# pca20053_sheet2_nrf5340_mcu.net
KiCad netlist of a schematic drawn in Altium Designer
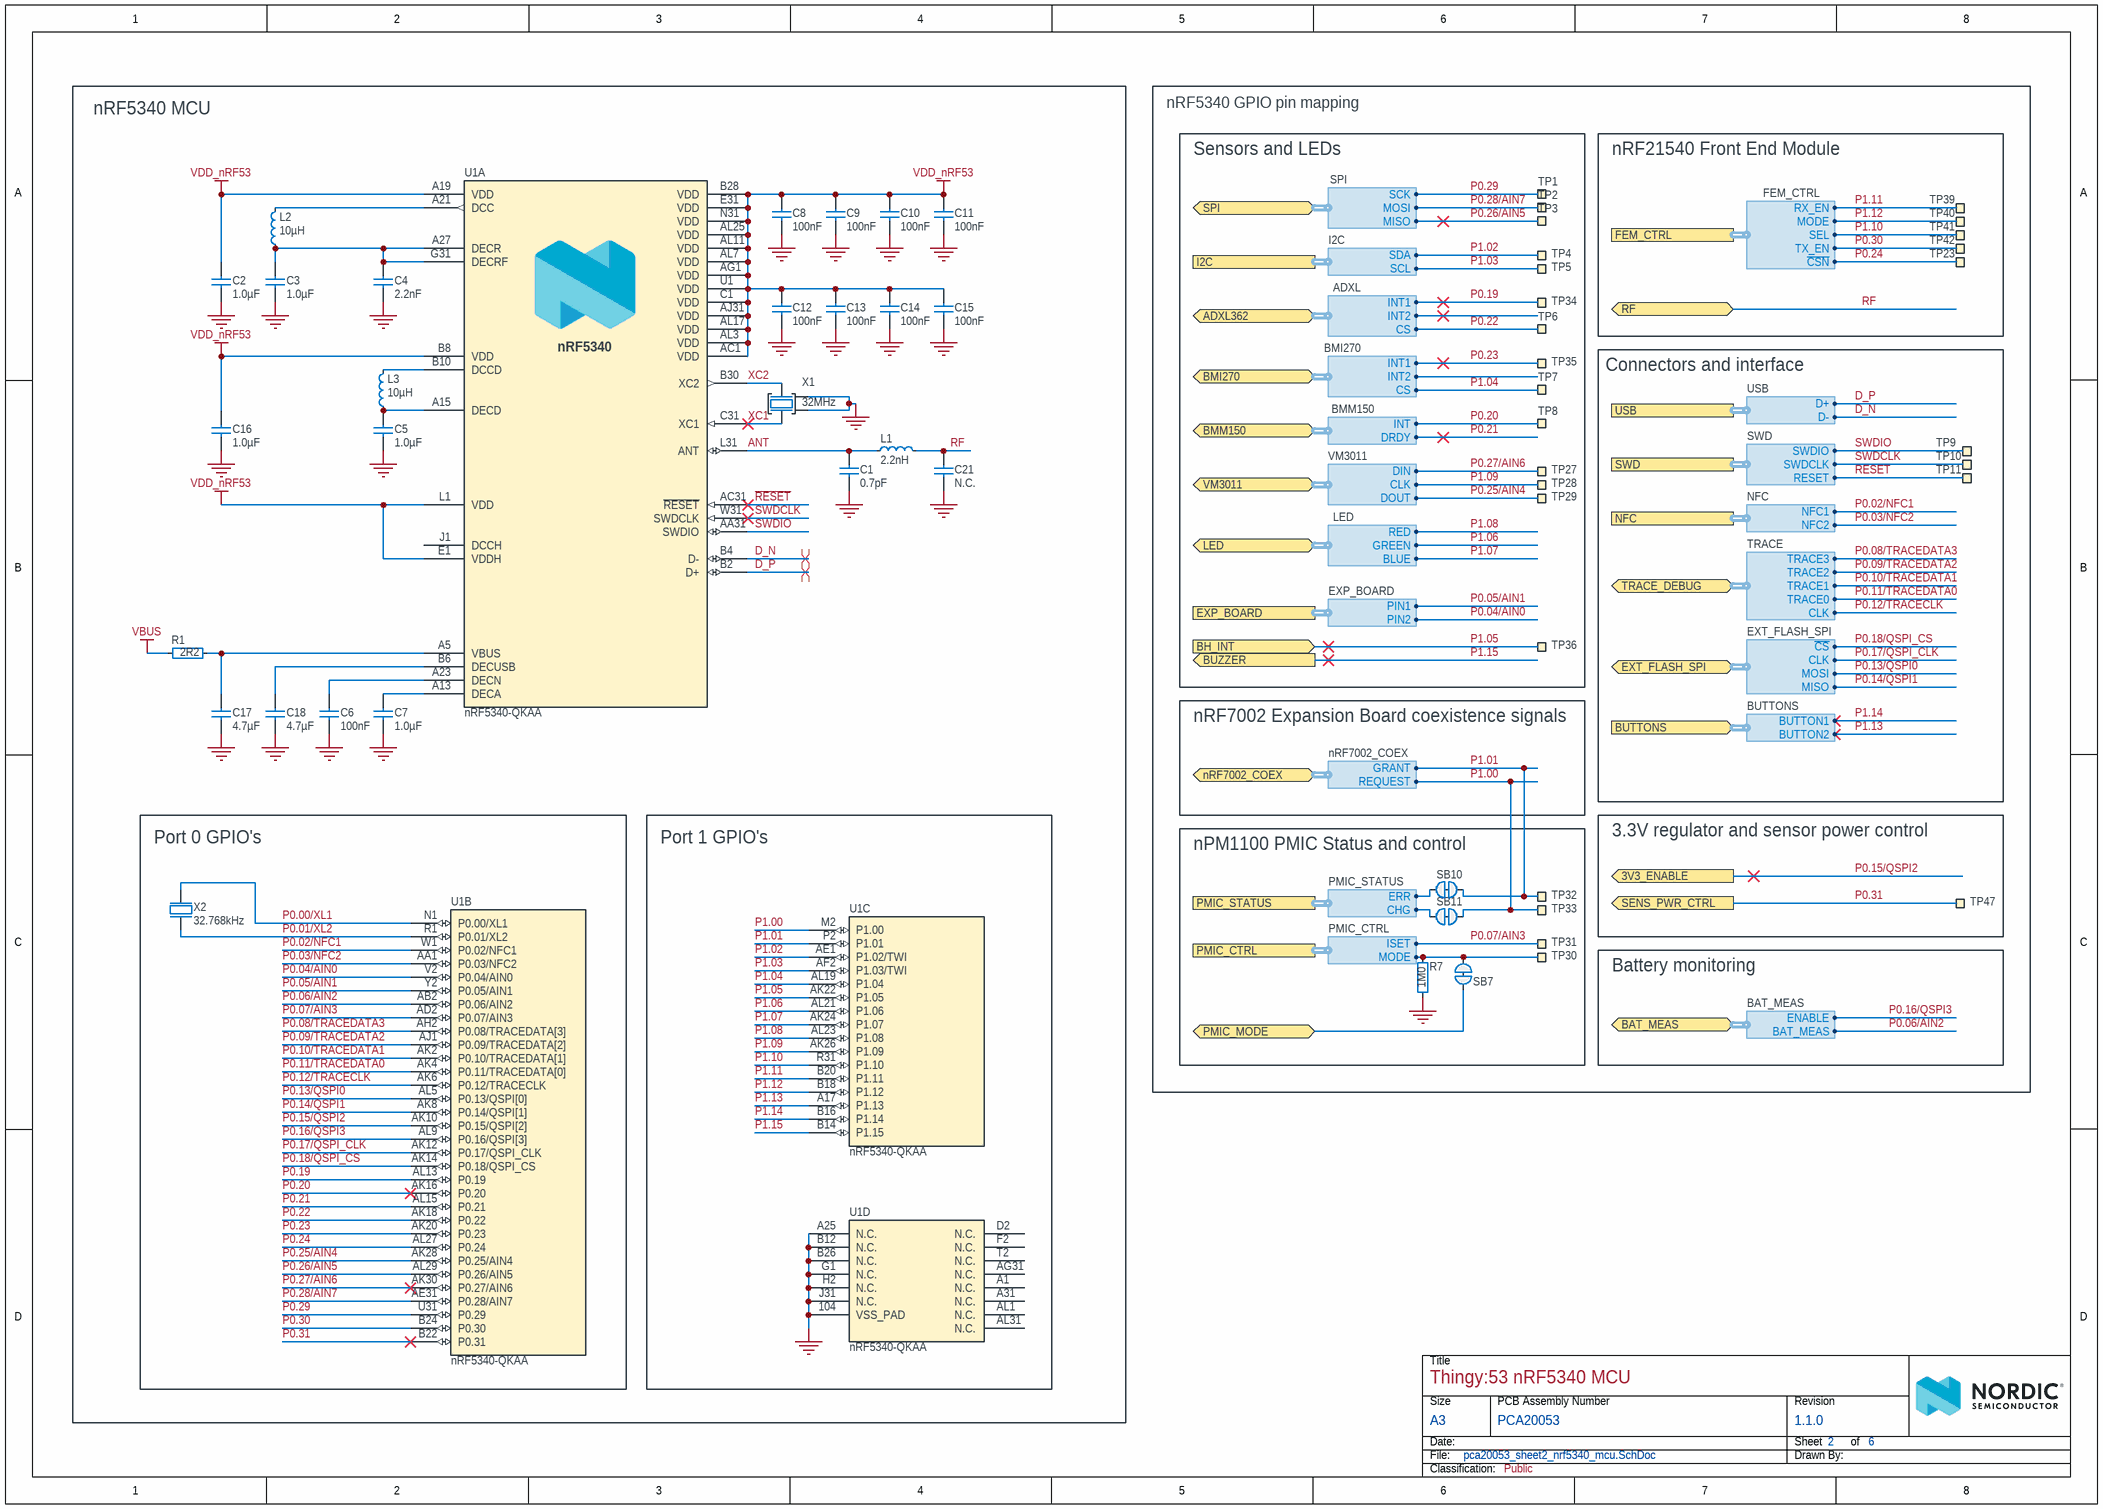
[diagram p0: pca20053_sheet2_nrf5340_mcu.SchDoc]

(export (version "E")
  (design (tool "Eeschema 10.0.6"))
  (components
    (comp (ref "C1")
      (value "0.7pF")
      (footprint "CAPC0603X03L_C")
      (description "Capacitor, Ceramic, C0G, ±0.05pF, 50V")
      (fields
        (field (name "PART NUMBER") "C0201-0.7p-50V-C0G-GJM0335C1HR70WB01")
        (field (name "MANUFACTURER") "Murata")
        (field (name "AUTHOR") "rsk")
      )
      (libsource (lib "AltiumLib") (part "CAP"))
    )
    (comp (ref "C2")
      (value "1.0µF")
      (footprint "CAPC1005X04L")
      (description "Capacitor, Ceramic, X5R, ±10%, 25V")
      (fields
        (field (name "PART NUMBER") "C0402-1µ0-25V-X5R")
        (field (name "MANUFACTURER") "Murata")
        (field (name "AUTHOR") "rsk")
      )
      (libsource (lib "AltiumLib") (part "CAP"))
    )
    (comp (ref "C3")
      (value "1.0µF")
      (footprint "CAPC1005X04L")
      (description "Capacitor, Ceramic, X5R, ±10%, 25V")
      (fields
        (field (name "PART NUMBER") "C0402-1µ0-25V-X5R")
        (field (name "MANUFACTURER") "Murata")
        (field (name "AUTHOR") "rsk")
      )
      (libsource (lib "AltiumLib") (part "CAP"))
    )
    (comp (ref "C4")
      (value "2.2nF")
      (footprint "CAPC0603X03L_C")
      (description "Capacitor, Ceramic, X5R, ±10%, 10V")
      (fields
        (field (name "PART NUMBER") "C0201-2n2-10V-X5R")
        (field (name "MANUFACTURER") "Murata")
        (field (name "AUTHOR") "rsk")
      )
      (libsource (lib "AltiumLib") (part "CAP"))
    )
    (comp (ref "C5")
      (value "1.0µF")
      (footprint "CAPC1005X04L")
      (description "Capacitor, Ceramic, X5R, ±10%, 25V")
      (fields
        (field (name "PART NUMBER") "C0402-1µ0-25V-X5R")
        (field (name "MANUFACTURER") "Murata")
        (field (name "AUTHOR") "rsk")
      )
      (libsource (lib "AltiumLib") (part "CAP"))
    )
    (comp (ref "C6")
      (value "100nF")
      (footprint "CAPC0603X03L_C")
      (description "Capacitor, Ceramic, X5R, ±10%, 6.3V")
      (fields
        (field (name "PART NUMBER") "C0201-100n-6.3V-X5R")
        (field (name "MANUFACTURER") "Murata")
        (field (name "AUTHOR") "rsk")
      )
      (libsource (lib "AltiumLib") (part "CAP"))
    )
    (comp (ref "C7")
      (value "1.0µF")
      (footprint "CAPC1005X04L")
      (description "Capacitor, Ceramic, X5R, ±10%, 25V")
      (fields
        (field (name "PART NUMBER") "C0402-1µ0-25V-X5R")
        (field (name "MANUFACTURER") "Murata")
        (field (name "AUTHOR") "rsk")
      )
      (libsource (lib "AltiumLib") (part "CAP"))
    )
    (comp (ref "C8")
      (value "100nF")
      (footprint "CAPC0603X03L_C")
      (description "Capacitor, Ceramic, X5R, ±10%, 6.3V")
      (fields
        (field (name "PART NUMBER") "C0201-100n-6.3V-X5R")
        (field (name "MANUFACTURER") "Murata")
        (field (name "AUTHOR") "rsk")
      )
      (libsource (lib "AltiumLib") (part "CAP"))
    )
    (comp (ref "C9")
      (value "100nF")
      (footprint "CAPC0603X03L_C")
      (description "Capacitor, Ceramic, X5R, ±10%, 6.3V")
      (fields
        (field (name "PART NUMBER") "C0201-100n-6.3V-X5R")
        (field (name "MANUFACTURER") "Murata")
        (field (name "AUTHOR") "rsk")
      )
      (libsource (lib "AltiumLib") (part "CAP"))
    )
    (comp (ref "C10")
      (value "100nF")
      (footprint "CAPC0603X03L_C")
      (description "Capacitor, Ceramic, X5R, ±10%, 6.3V")
      (fields
        (field (name "PART NUMBER") "C0201-100n-6.3V-X5R")
        (field (name "MANUFACTURER") "Murata")
        (field (name "AUTHOR") "rsk")
      )
      (libsource (lib "AltiumLib") (part "CAP"))
    )
    (comp (ref "C11")
      (value "100nF")
      (footprint "CAPC0603X03L_C")
      (description "Capacitor, Ceramic, X5R, ±10%, 6.3V")
      (fields
        (field (name "PART NUMBER") "C0201-100n-6.3V-X5R")
        (field (name "MANUFACTURER") "Murata")
        (field (name "AUTHOR") "rsk")
      )
      (libsource (lib "AltiumLib") (part "CAP"))
    )
    (comp (ref "C12")
      (value "100nF")
      (footprint "CAPC0603X03L_C")
      (description "Capacitor, Ceramic, X5R, ±10%, 6.3V")
      (fields
        (field (name "PART NUMBER") "C0201-100n-6.3V-X5R")
        (field (name "MANUFACTURER") "Murata")
        (field (name "AUTHOR") "rsk")
      )
      (libsource (lib "AltiumLib") (part "CAP"))
    )
    (comp (ref "C13")
      (value "100nF")
      (footprint "CAPC0603X03L_C")
      (description "Capacitor, Ceramic, X5R, ±10%, 6.3V")
      (fields
        (field (name "PART NUMBER") "C0201-100n-6.3V-X5R")
        (field (name "MANUFACTURER") "Murata")
        (field (name "AUTHOR") "rsk")
      )
      (libsource (lib "AltiumLib") (part "CAP"))
    )
    (comp (ref "C14")
      (value "100nF")
      (footprint "CAPC0603X03L_C")
      (description "Capacitor, Ceramic, X5R, ±10%, 6.3V")
      (fields
        (field (name "PART NUMBER") "C0201-100n-6.3V-X5R")
        (field (name "MANUFACTURER") "Murata")
        (field (name "AUTHOR") "rsk")
      )
      (libsource (lib "AltiumLib") (part "CAP"))
    )
    (comp (ref "C15")
      (value "100nF")
      (footprint "CAPC0603X03L_C")
      (description "Capacitor, Ceramic, X5R, ±10%, 6.3V")
      (fields
        (field (name "PART NUMBER") "C0201-100n-6.3V-X5R")
        (field (name "MANUFACTURER") "Murata")
        (field (name "AUTHOR") "rsk")
      )
      (libsource (lib "AltiumLib") (part "CAP"))
    )
    (comp (ref "C16")
      (value "1.0µF")
      (footprint "CAPC1005X04L")
      (description "Capacitor, Ceramic, X5R, ±10%, 25V")
      (fields
        (field (name "PART NUMBER") "C0402-1µ0-25V-X5R")
        (field (name "MANUFACTURER") "Murata")
        (field (name "AUTHOR") "rsk")
      )
      (libsource (lib "AltiumLib") (part "CAP"))
    )
    (comp (ref "C17")
      (value "4.7µF")
      (footprint "CAPC1608X06L")
      (description "Capacitor, X5R, ±10%, 25V")
      (fields
        (field (name "PART NUMBER") "C0603-4µ7-25V-X5R")
        (field (name "MANUFACTURER") "Murata")
        (field (name "AUTHOR") "rsk")
      )
      (libsource (lib "AltiumLib") (part "CAP"))
    )
    (comp (ref "C18")
      (value "4.7µF")
      (footprint "CAPC1608X06L")
      (description "Capacitor, X5R, ±10%, 25V")
      (fields
        (field (name "PART NUMBER") "C0603-4µ7-25V-X5R")
        (field (name "MANUFACTURER") "Murata")
        (field (name "AUTHOR") "rsk")
      )
      (libsource (lib "AltiumLib") (part "CAP"))
    )
    (comp (ref "C21")
      (value "N.C.")
      (footprint "CAPC0603X03L_C_NC")
      (description "Not mounted")
      (fields
        (field (name "PART NUMBER") "C0201-N.C.")
        (field (name "MANUFACTURER") "N.A.")
        (field (name "AUTHOR") "rsk")
      )
      (libsource (lib "AltiumLib") (part "CAP"))
    )
    (comp (ref "L1")
      (value "2.2nH")
      (footprint "INDC0603X03L_C")
      (description "Inductor, 600mA, ±0.1ｎH, 120mOhm")
      (fields
        (field (name "PART NUMBER") "L0201-2n2-HQ-Murata")
        (field (name "MANUFACTURER") "Murata")
        (field (name "AUTHOR") "rsk")
      )
      (libsource (lib "AltiumLib") (part "IND"))
    )
    (comp (ref "L2")
      (value "10µH")
      (footprint "INDC1608X06L")
      (description "Inductor, 100mA, ±20%, 1.05Ohm")
      (fields
        (field (name "PART NUMBER") "L0603-10µ-Murata-DN")
        (field (name "MANUFACTURER") "Murata")
        (field (name "AUTHOR") "rubr")
      )
      (libsource (lib "") (part "IND_1"))
    )
    (comp (ref "L3")
      (value "10µH")
      (footprint "INDC1608X06L")
      (description "Inductor, 100mA, ±20%, 1.05Ohm")
      (fields
        (field (name "PART NUMBER") "L0603-10µ-Murata-DN")
        (field (name "MANUFACTURER") "Murata")
        (field (name "AUTHOR") "rubr")
      )
      (libsource (lib "") (part "IND_1"))
    )
    (comp (ref "R1")
      (value "2R2")
      (footprint "RESC0603X03L_C")
      (description "Resistor, ±1%, 0.05W")
      (fields
        (field (name "PART NUMBER") "R0201-2R2")
        (field (name "MANUFACTURER") "N.A.")
        (field (name "AUTHOR") "rsk")
      )
      (libsource (lib "AltiumLib") (part "RES"))
    )
    (comp (ref "R7")
      (value "1M0")
      (footprint "RESC0603X03L_C")
      (description "Resistor, ±1%, 0.05W")
      (fields
        (field (name "PART NUMBER") "R0201-1M0")
        (field (name "MANUFACTURER") "N.A.")
        (field (name "AUTHOR") "rsk")
      )
      (libsource (lib "AltiumLib") (part "RES"))
    )
    (comp (ref "SB7")
      (value "Solderbridge")
      (footprint "Solderbridge_Shorted")
      (description "Shorted Solderbridge")
      (fields
        (field (name "PART NUMBER") "Solderbridge Shorted")
        (field (name "MANUFACTURER") "N.A.")
        (field (name "AUTHOR") "rsk")
      )
      (libsource (lib "AltiumLib") (part "SOLDERBRIDGE_SHORTED"))
    )
    (comp (ref "SB10")
      (value "Solderbridge")
      (footprint "Solderbridge_Shorted")
      (description "Shorted Solderbridge")
      (fields
        (field (name "PART NUMBER") "Solderbridge Shorted")
        (field (name "MANUFACTURER") "N.A.")
        (field (name "AUTHOR") "rsk")
      )
      (libsource (lib "AltiumLib") (part "SOLDERBRIDGE_SHORTED"))
    )
    (comp (ref "SB11")
      (value "Solderbridge")
      (footprint "Solderbridge_Shorted")
      (description "Shorted Solderbridge")
      (fields
        (field (name "PART NUMBER") "Solderbridge Shorted")
        (field (name "MANUFACTURER") "N.A.")
        (field (name "AUTHOR") "rsk")
      )
      (libsource (lib "AltiumLib") (part "SOLDERBRIDGE_SHORTED"))
    )
    (comp (ref "TP1")
      (value "Ø1.5mm,SMD")
      (footprint "TP_SMD_D1.5mm")
      (description "1.5mm circular SMD testpad")
      (fields
        (field (name "PART NUMBER") "TP_SMD_Ø1.5MM")
        (field (name "MANUFACTURER") "Nordic Semiconductor")
        (field (name "AUTHOR") "rsk")
      )
      (libsource (lib "") (part "TESTPAD_1"))
    )
    (comp (ref "TP2")
      (value "Ø1.5mm,SMD")
      (footprint "TP_SMD_D1.5mm")
      (description "1.5mm circular SMD testpad")
      (fields
        (field (name "PART NUMBER") "TP_SMD_Ø1.5MM")
        (field (name "MANUFACTURER") "Nordic Semiconductor")
        (field (name "AUTHOR") "rsk")
      )
      (libsource (lib "") (part "TESTPAD_1"))
    )
    (comp (ref "TP3")
      (value "Ø1.5mm,SMD")
      (footprint "TP_SMD_D1.5mm")
      (description "1.5mm circular SMD testpad")
      (fields
        (field (name "PART NUMBER") "TP_SMD_Ø1.5MM")
        (field (name "MANUFACTURER") "Nordic Semiconductor")
        (field (name "AUTHOR") "rsk")
      )
      (libsource (lib "") (part "TESTPAD_1"))
    )
    (comp (ref "TP4")
      (value "Ø1.5mm,SMD")
      (footprint "TP_SMD_D1.5mm")
      (description "1.5mm circular SMD testpad")
      (fields
        (field (name "PART NUMBER") "TP_SMD_Ø1.5MM")
        (field (name "MANUFACTURER") "Nordic Semiconductor")
        (field (name "AUTHOR") "rsk")
      )
      (libsource (lib "AltiumLib") (part "TESTPAD"))
    )
    (comp (ref "TP5")
      (value "Ø1.5mm,SMD")
      (footprint "TP_SMD_D1.5mm")
      (description "1.5mm circular SMD testpad")
      (fields
        (field (name "PART NUMBER") "TP_SMD_Ø1.5MM")
        (field (name "MANUFACTURER") "Nordic Semiconductor")
        (field (name "AUTHOR") "rsk")
      )
      (libsource (lib "AltiumLib") (part "TESTPAD"))
    )
    (comp (ref "TP6")
      (value "Ø1.0mm,SMD")
      (footprint "TP_SMD_D1.0mm")
      (description "1.0mm circular SMD testpad")
      (fields
        (field (name "PART NUMBER") "TP_SMD_Ø1.0MM")
        (field (name "MANUFACTURER") "Nordic Semiconductor")
        (field (name "AUTHOR") "rsk")
      )
      (libsource (lib "") (part "TESTPAD_1"))
    )
    (comp (ref "TP7")
      (value "Ø1.0mm,SMD")
      (footprint "TP_SMD_D1.0mm")
      (description "1.0mm circular SMD testpad")
      (fields
        (field (name "PART NUMBER") "TP_SMD_Ø1.0MM")
        (field (name "MANUFACTURER") "Nordic Semiconductor")
        (field (name "AUTHOR") "rsk")
      )
      (libsource (lib "") (part "TESTPAD_1"))
    )
    (comp (ref "TP8")
      (value "Ø1.0mm,SMD")
      (footprint "TP_SMD_D1.0mm")
      (description "1.0mm circular SMD testpad")
      (fields
        (field (name "PART NUMBER") "TP_SMD_Ø1.0MM")
        (field (name "MANUFACTURER") "Nordic Semiconductor")
        (field (name "AUTHOR") "rsk")
      )
      (libsource (lib "") (part "TESTPAD_1"))
    )
    (comp (ref "TP9")
      (value "Ø1.5mm,SMD")
      (footprint "TP_SMD_D1.5mm")
      (description "1.5mm circular SMD testpad")
      (fields
        (field (name "PART NUMBER") "TP_SMD_Ø1.5MM")
        (field (name "MANUFACTURER") "Nordic Semiconductor")
        (field (name "AUTHOR") "rsk")
      )
      (libsource (lib "AltiumLib") (part "TESTPAD"))
    )
    (comp (ref "TP10")
      (value "Ø1.5mm,SMD")
      (footprint "TP_SMD_D1.5mm")
      (description "1.5mm circular SMD testpad")
      (fields
        (field (name "PART NUMBER") "TP_SMD_Ø1.5MM")
        (field (name "MANUFACTURER") "Nordic Semiconductor")
        (field (name "AUTHOR") "rsk")
      )
      (libsource (lib "AltiumLib") (part "TESTPAD"))
    )
    (comp (ref "TP11")
      (value "Ø1.5mm,SMD")
      (footprint "TP_SMD_D1.5mm")
      (description "1.5mm circular SMD testpad")
      (fields
        (field (name "PART NUMBER") "TP_SMD_Ø1.5MM")
        (field (name "MANUFACTURER") "Nordic Semiconductor")
        (field (name "AUTHOR") "rsk")
      )
      (libsource (lib "AltiumLib") (part "TESTPAD"))
    )
    (comp (ref "TP23")
      (value "Ø1.5mm,SMD")
      (footprint "TP_SMD_D1.5mm")
      (description "1.5mm circular SMD testpad")
      (fields
        (field (name "PART NUMBER") "TP_SMD_Ø1.5MM")
        (field (name "MANUFACTURER") "Nordic Semiconductor")
        (field (name "AUTHOR") "rsk")
      )
      (libsource (lib "AltiumLib") (part "TESTPAD"))
    )
    (comp (ref "TP27")
      (value "Ø0.7mm,SMD")
      (footprint "TP_SMD_D0.7mm")
      (description "0.7mm circular SMD testpad")
      (fields
        (field (name "PART NUMBER") "TP_SMD_Ø0.7MM")
        (field (name "MANUFACTURER") "Nordic Semiconductor")
        (field (name "AUTHOR") "rsk")
      )
      (libsource (lib "AltiumLib") (part "TESTPAD"))
    )
    (comp (ref "TP28")
      (value "Ø0.7mm,SMD")
      (footprint "TP_SMD_D0.7mm")
      (description "0.7mm circular SMD testpad")
      (fields
        (field (name "PART NUMBER") "TP_SMD_Ø0.7MM")
        (field (name "MANUFACTURER") "Nordic Semiconductor")
        (field (name "AUTHOR") "rsk")
      )
      (libsource (lib "AltiumLib") (part "TESTPAD"))
    )
    (comp (ref "TP29")
      (value "Ø0.7mm,SMD")
      (footprint "TP_SMD_D0.7mm")
      (description "0.7mm circular SMD testpad")
      (fields
        (field (name "PART NUMBER") "TP_SMD_Ø0.7MM")
        (field (name "MANUFACTURER") "Nordic Semiconductor")
        (field (name "AUTHOR") "rsk")
      )
      (libsource (lib "AltiumLib") (part "TESTPAD"))
    )
    (comp (ref "TP30")
      (value "Ø0.7mm,SMD")
      (footprint "TP_SMD_D0.7mm")
      (description "0.7mm circular SMD testpad")
      (fields
        (field (name "PART NUMBER") "TP_SMD_Ø0.7MM")
        (field (name "MANUFACTURER") "Nordic Semiconductor")
        (field (name "AUTHOR") "rsk")
      )
      (libsource (lib "AltiumLib") (part "TESTPAD"))
    )
    (comp (ref "TP31")
      (value "Ø0.7mm,SMD")
      (footprint "TP_SMD_D0.7mm")
      (description "0.7mm circular SMD testpad")
      (fields
        (field (name "PART NUMBER") "TP_SMD_Ø0.7MM")
        (field (name "MANUFACTURER") "Nordic Semiconductor")
        (field (name "AUTHOR") "rsk")
      )
      (libsource (lib "AltiumLib") (part "TESTPAD"))
    )
    (comp (ref "TP32")
      (value "Ø1.5mm,SMD")
      (footprint "TP_SMD_D1.5mm")
      (description "1.5mm circular SMD testpad")
      (fields
        (field (name "PART NUMBER") "TP_SMD_Ø1.5MM")
        (field (name "MANUFACTURER") "Nordic Semiconductor")
        (field (name "AUTHOR") "rsk")
      )
      (libsource (lib "AltiumLib") (part "TESTPAD"))
    )
    (comp (ref "TP33")
      (value "Ø1.5mm,SMD")
      (footprint "TP_SMD_D1.5mm")
      (description "1.5mm circular SMD testpad")
      (fields
        (field (name "PART NUMBER") "TP_SMD_Ø1.5MM")
        (field (name "MANUFACTURER") "Nordic Semiconductor")
        (field (name "AUTHOR") "rsk")
      )
      (libsource (lib "AltiumLib") (part "TESTPAD"))
    )
    (comp (ref "TP34")
      (value "Ø0.7mm,SMD")
      (footprint "TP_SMD_D0.7mm")
      (description "0.7mm circular SMD testpad")
      (fields
        (field (name "PART NUMBER") "TP_SMD_Ø0.7MM")
        (field (name "MANUFACTURER") "Nordic Semiconductor")
        (field (name "AUTHOR") "rsk")
      )
      (libsource (lib "AltiumLib") (part "TESTPAD"))
    )
    (comp (ref "TP35")
      (value "Ø0.7mm,SMD")
      (footprint "TP_SMD_D0.7mm")
      (description "0.7mm circular SMD testpad")
      (fields
        (field (name "PART NUMBER") "TP_SMD_Ø0.7MM")
        (field (name "MANUFACTURER") "Nordic Semiconductor")
        (field (name "AUTHOR") "rsk")
      )
      (libsource (lib "AltiumLib") (part "TESTPAD"))
    )
    (comp (ref "TP36")
      (value "Ø0.7mm,SMD")
      (footprint "TP_SMD_D0.7mm")
      (description "0.7mm circular SMD testpad")
      (fields
        (field (name "PART NUMBER") "TP_SMD_Ø0.7MM")
        (field (name "MANUFACTURER") "Nordic Semiconductor")
        (field (name "AUTHOR") "rsk")
      )
      (libsource (lib "AltiumLib") (part "TESTPAD"))
    )
    (comp (ref "TP39")
      (value "Ø1.5mm,SMD")
      (footprint "TP_SMD_D1.5mm")
      (description "1.5mm circular SMD testpad")
      (fields
        (field (name "PART NUMBER") "TP_SMD_Ø1.5MM")
        (field (name "MANUFACTURER") "Nordic Semiconductor")
        (field (name "AUTHOR") "rsk")
      )
      (libsource (lib "AltiumLib") (part "TESTPAD"))
    )
    (comp (ref "TP40")
      (value "Ø1.5mm,SMD")
      (footprint "TP_SMD_D1.5mm")
      (description "1.5mm circular SMD testpad")
      (fields
        (field (name "PART NUMBER") "TP_SMD_Ø1.5MM")
        (field (name "MANUFACTURER") "Nordic Semiconductor")
        (field (name "AUTHOR") "rsk")
      )
      (libsource (lib "AltiumLib") (part "TESTPAD"))
    )
    (comp (ref "TP41")
      (value "Ø1.5mm,SMD")
      (footprint "TP_SMD_D1.5mm")
      (description "1.5mm circular SMD testpad")
      (fields
        (field (name "PART NUMBER") "TP_SMD_Ø1.5MM")
        (field (name "MANUFACTURER") "Nordic Semiconductor")
        (field (name "AUTHOR") "rsk")
      )
      (libsource (lib "AltiumLib") (part "TESTPAD"))
    )
    (comp (ref "TP42")
      (value "Ø1.5mm,SMD")
      (footprint "TP_SMD_D1.5mm")
      (description "1.5mm circular SMD testpad")
      (fields
        (field (name "PART NUMBER") "TP_SMD_Ø1.5MM")
        (field (name "MANUFACTURER") "Nordic Semiconductor")
        (field (name "AUTHOR") "rsk")
      )
      (libsource (lib "AltiumLib") (part "TESTPAD"))
    )
    (comp (ref "TP47")
      (value "Ø0.7mm,SMD")
      (footprint "TP_SMD_D0.7mm")
      (description "0.7mm circular SMD testpad")
      (fields
        (field (name "PART NUMBER") "TP_SMD_Ø0.7MM")
        (field (name "MANUFACTURER") "Nordic Semiconductor")
        (field (name "AUTHOR") "rsk")
      )
      (libsource (lib "AltiumLib") (part "TESTPAD"))
    )
    (comp (ref "U1")
      (value "nRF5340-QKAA")
      (footprint "AQFN40P700X700X85_HS-99N")
      (description "Multi-protocol Bluetooth Low Energy, IEEE 802.15.4, ANT and 2.4GHz proprietary system-on-chip")
      (fields
        (field (name "PART NUMBER") "nRF5340-QKAAD0")
        (field (name "MANUFACTURER") "Nordic Semiconductor")
        (field (name "AUTHOR") "rsk")
      )
      (libsource (lib "AltiumLib") (part "nRF5340_QKAA"))
    )
    (comp (ref "X1")
      (value "32MHz")
      (footprint "BT-XTAL_2016")
      (description "XTAL SMD 2016, 32MHz, Cl=8pF, Tol: ±10ppm, Stab: ±10ppm")
      (fields
        (field (name "PART NUMBER") "XRCGB32M000F1S1BR0")
        (field (name "MANUFACTURER") "Murata")
        (field (name "AUTHOR") "rsk")
      )
      (libsource (lib "AltiumLib") (part "XTAL_4-pin"))
    )
    (comp (ref "X2")
      (value "32.768kHz")
      (footprint "XTAL_2012")
      (description "XTAL SMD 2012, 32.768kHz, 9pF, ±20ppm")
      (fields
        (field (name "PART NUMBER") "XTAL_SMD2012_32.768kHz_9pF_MC")
        (field (name "MANUFACTURER") "Micro Crystal")
        (field (name "AUTHOR") "rsk")
      )
      (libsource (lib "AltiumLib") (part "XTAL_2-pin"))
    )
  )
  (nets
    (net (code "20") (name "/ANT") (class "Default")
      (node (ref "C1") (pin "2") (pinfunction "2_2") (pintype "passive"))
      (node (ref "L1") (pin "2") (pinfunction "2_2") (pintype "passive"))
      (node (ref "U1") (pin "L31") (pinfunction "ANT_L31") (pintype "bidirectional"))
    )
    (net (code "21") (name "/CHG") (class "Default")
      (node (ref "SB11") (pin "2") (pinfunction "1_2") (pintype "passive"))
    )
    (net (code "22") (name "/D_N") (class "Default")
      (node (ref "U1") (pin "B4") (pinfunction "D-_B4") (pintype "bidirectional"))
    )
    (net (code "23") (name "/D_P") (class "Default")
      (node (ref "U1") (pin "B2") (pinfunction "D+_B2") (pintype "bidirectional"))
    )
    (net (code "24") (name "/ERR") (class "Default")
      (node (ref "SB10") (pin "2") (pinfunction "1_2") (pintype "passive"))
    )
    (net (code "25") (name "/P0.00{slash}XL1") (class "Default")
      (node (ref "U1") (pin "N1") (pinfunction "P0.00/XL1_N1") (pintype "bidirectional"))
      (node (ref "X2") (pin "1") (pinfunction "inp_1") (pintype "passive"))
    )
    (net (code "26") (name "/P0.01{slash}XL2") (class "Default")
      (node (ref "U1") (pin "R1") (pinfunction "P0.01/XL2_R1") (pintype "bidirectional"))
      (node (ref "X2") (pin "2") (pinfunction "out_2") (pintype "passive"))
    )
    (net (code "27") (name "/P0.02{slash}NFC1") (class "Default")
      (node (ref "U1") (pin "W1") (pinfunction "P0.02/NFC1_W1") (pintype "bidirectional"))
    )
    (net (code "28") (name "/P0.03{slash}NFC2") (class "Default")
      (node (ref "U1") (pin "AA1") (pinfunction "P0.03/NFC2_AA1") (pintype "bidirectional"))
    )
    (net (code "29") (name "/P0.04{slash}AIN0") (class "Default")
      (node (ref "U1") (pin "V2") (pinfunction "P0.04/AIN0_V2") (pintype "bidirectional"))
    )
    (net (code "30") (name "/P0.05{slash}AIN1") (class "Default")
      (node (ref "U1") (pin "Y2") (pinfunction "P0.05/AIN1_Y2") (pintype "bidirectional"))
    )
    (net (code "31") (name "/P0.06{slash}AIN2") (class "Default")
      (node (ref "U1") (pin "AB2") (pinfunction "P0.06/AIN2_AB2") (pintype "bidirectional"))
    )
    (net (code "32") (name "/P0.07{slash}AIN3") (class "Default")
      (node (ref "TP31") (pin "1") (pinfunction "1_1") (pintype "passive"))
      (node (ref "U1") (pin "AD2") (pinfunction "P0.07/AIN3_AD2") (pintype "bidirectional"))
    )
    (net (code "33") (name "/P0.08{slash}TRACEDATA3") (class "Default")
      (node (ref "U1") (pin "AH2") (pinfunction "P0.08/TRACEDATA[3]_AH2") (pintype "bidirectional"))
    )
    (net (code "34") (name "/P0.09{slash}TRACEDATA2") (class "Default")
      (node (ref "U1") (pin "AJ1") (pinfunction "P0.09/TRACEDATA[2]_AJ1") (pintype "bidirectional"))
    )
    (net (code "35") (name "/P0.10{slash}TRACEDATA1") (class "Default")
      (node (ref "U1") (pin "AK2") (pinfunction "P0.10/TRACEDATA[1]_AK2") (pintype "bidirectional"))
    )
    (net (code "36") (name "/P0.11{slash}TRACEDATA0") (class "Default")
      (node (ref "U1") (pin "AK4") (pinfunction "P0.11/TRACEDATA[0]_AK4") (pintype "bidirectional"))
    )
    (net (code "37") (name "/P0.12{slash}TRACECLK") (class "Default")
      (node (ref "U1") (pin "AK6") (pinfunction "P0.12/TRACECLK_AK6") (pintype "bidirectional"))
    )
    (net (code "38") (name "/P0.13{slash}QSPI0") (class "Default")
      (node (ref "U1") (pin "AL5") (pinfunction "P0.13/QSPI[0]_AL5") (pintype "bidirectional"))
    )
    (net (code "39") (name "/P0.14{slash}QSPI1") (class "Default")
      (node (ref "U1") (pin "AK8") (pinfunction "P0.14/QSPI[1]_AK8") (pintype "bidirectional"))
    )
    (net (code "40") (name "/P0.15{slash}QSPI2") (class "Default")
      (node (ref "U1") (pin "AK10") (pinfunction "P0.15/QSPI[2]_AK10") (pintype "bidirectional"))
    )
    (net (code "41") (name "/P0.16{slash}QSPI3") (class "Default")
      (node (ref "U1") (pin "AL9") (pinfunction "P0.16/QSPI[3]_AL9") (pintype "bidirectional"))
    )
    (net (code "42") (name "/P0.17{slash}QSPI_CLK") (class "Default")
      (node (ref "U1") (pin "AK12") (pinfunction "P0.17/QSPI_CLK_AK12") (pintype "bidirectional"))
    )
    (net (code "43") (name "/P0.18{slash}QSPI_CS") (class "Default")
      (node (ref "U1") (pin "AK14") (pinfunction "P0.18/QSPI_CS_AK14") (pintype "bidirectional"))
    )
    (net (code "44") (name "/P0.19") (class "Default")
      (node (ref "TP34") (pin "1") (pinfunction "1_1") (pintype "passive"))
      (node (ref "U1") (pin "AL13") (pinfunction "P0.19_AL13") (pintype "bidirectional"))
    )
    (net (code "45") (name "/P0.20") (class "Default")
      (node (ref "TP8") (pin "1") (pinfunction "1_1") (pintype "passive"))
      (node (ref "U1") (pin "AK16") (pinfunction "P0.20_AK16") (pintype "bidirectional"))
    )
    (net (code "46") (name "/P0.21") (class "Default")
      (node (ref "U1") (pin "AL15") (pinfunction "P0.21_AL15") (pintype "bidirectional"))
    )
    (net (code "47") (name "/P0.22") (class "Default")
      (node (ref "TP6") (pin "1") (pinfunction "1_1") (pintype "passive"))
      (node (ref "U1") (pin "AK18") (pinfunction "P0.22_AK18") (pintype "bidirectional"))
    )
    (net (code "48") (name "/P0.23") (class "Default")
      (node (ref "TP35") (pin "1") (pinfunction "1_1") (pintype "passive"))
      (node (ref "U1") (pin "AK20") (pinfunction "P0.23_AK20") (pintype "bidirectional"))
    )
    (net (code "49") (name "/P0.24") (class "Default")
      (node (ref "TP23") (pin "1") (pinfunction "1_1") (pintype "passive"))
      (node (ref "U1") (pin "AL27") (pinfunction "P0.24_AL27") (pintype "bidirectional"))
    )
    (net (code "50") (name "/P0.25{slash}AIN4") (class "Default")
      (node (ref "TP29") (pin "1") (pinfunction "1_1") (pintype "passive"))
      (node (ref "U1") (pin "AK28") (pinfunction "P0.25/AIN4_AK28") (pintype "bidirectional"))
    )
    (net (code "51") (name "/P0.26{slash}AIN5") (class "Default")
      (node (ref "TP3") (pin "1") (pinfunction "1_1") (pintype "passive"))
      (node (ref "U1") (pin "AL29") (pinfunction "P0.26/AIN5_AL29") (pintype "bidirectional"))
    )
    (net (code "52") (name "/P0.27{slash}AIN6") (class "Default")
      (node (ref "TP27") (pin "1") (pinfunction "1_1") (pintype "passive"))
      (node (ref "U1") (pin "AK30") (pinfunction "P0.27/AIN6_AK30") (pintype "bidirectional"))
    )
    (net (code "53") (name "/P0.28{slash}AIN7") (class "Default")
      (node (ref "TP2") (pin "1") (pinfunction "1_1") (pintype "passive"))
      (node (ref "U1") (pin "AE31") (pinfunction "P0.28/AIN7_AE31") (pintype "bidirectional"))
    )
    (net (code "54") (name "/P0.29") (class "Default")
      (node (ref "TP1") (pin "1") (pinfunction "1_1") (pintype "passive"))
      (node (ref "U1") (pin "U31") (pinfunction "P0.29_U31") (pintype "bidirectional"))
    )
    (net (code "55") (name "/P0.30") (class "Default")
      (node (ref "TP42") (pin "1") (pinfunction "1_1") (pintype "passive"))
      (node (ref "U1") (pin "B24") (pinfunction "P0.30_B24") (pintype "bidirectional"))
    )
    (net (code "56") (name "/P0.31") (class "Default")
      (node (ref "TP47") (pin "1") (pinfunction "1_1") (pintype "passive"))
      (node (ref "U1") (pin "B22") (pinfunction "P0.31_B22") (pintype "bidirectional"))
    )
    (net (code "57") (name "/P1.00") (class "Default")
      (node (ref "SB11") (pin "1") (pinfunction "0_1") (pintype "passive"))
      (node (ref "TP33") (pin "1") (pinfunction "1_1") (pintype "passive"))
      (node (ref "U1") (pin "M2") (pinfunction "P1.00_M2") (pintype "bidirectional"))
    )
    (net (code "58") (name "/P1.01") (class "Default")
      (node (ref "SB10") (pin "1") (pinfunction "0_1") (pintype "passive"))
      (node (ref "TP32") (pin "1") (pinfunction "1_1") (pintype "passive"))
      (node (ref "U1") (pin "P2") (pinfunction "P1.01_P2") (pintype "bidirectional"))
    )
    (net (code "59") (name "/P1.02") (class "Default")
      (node (ref "TP4") (pin "1") (pinfunction "1_1") (pintype "passive"))
      (node (ref "U1") (pin "AE1") (pinfunction "P1.02/TWI_AE1") (pintype "bidirectional"))
    )
    (net (code "60") (name "/P1.03") (class "Default")
      (node (ref "TP5") (pin "1") (pinfunction "1_1") (pintype "passive"))
      (node (ref "U1") (pin "AF2") (pinfunction "P1.03/TWI_AF2") (pintype "bidirectional"))
    )
    (net (code "61") (name "/P1.04") (class "Default")
      (node (ref "TP7") (pin "1") (pinfunction "1_1") (pintype "passive"))
      (node (ref "U1") (pin "AL19") (pinfunction "P1.04_AL19") (pintype "bidirectional"))
    )
    (net (code "62") (name "/P1.05") (class "Default")
      (node (ref "TP36") (pin "1") (pinfunction "1_1") (pintype "passive"))
      (node (ref "U1") (pin "AK22") (pinfunction "P1.05_AK22") (pintype "bidirectional"))
    )
    (net (code "63") (name "/P1.06") (class "Default")
      (node (ref "U1") (pin "AL21") (pinfunction "P1.06_AL21") (pintype "bidirectional"))
    )
    (net (code "64") (name "/P1.07") (class "Default")
      (node (ref "U1") (pin "AK24") (pinfunction "P1.07_AK24") (pintype "bidirectional"))
    )
    (net (code "65") (name "/P1.08") (class "Default")
      (node (ref "U1") (pin "AL23") (pinfunction "P1.08_AL23") (pintype "bidirectional"))
    )
    (net (code "66") (name "/P1.09") (class "Default")
      (node (ref "TP28") (pin "1") (pinfunction "1_1") (pintype "passive"))
      (node (ref "U1") (pin "AK26") (pinfunction "P1.09_AK26") (pintype "bidirectional"))
    )
    (net (code "67") (name "/P1.10") (class "Default")
      (node (ref "TP41") (pin "1") (pinfunction "1_1") (pintype "passive"))
      (node (ref "U1") (pin "R31") (pinfunction "P1.10_R31") (pintype "bidirectional"))
    )
    (net (code "68") (name "/P1.11") (class "Default")
      (node (ref "TP39") (pin "1") (pinfunction "1_1") (pintype "passive"))
      (node (ref "U1") (pin "B20") (pinfunction "P1.11_B20") (pintype "bidirectional"))
    )
    (net (code "69") (name "/P1.12") (class "Default")
      (node (ref "TP40") (pin "1") (pinfunction "1_1") (pintype "passive"))
      (node (ref "U1") (pin "B18") (pinfunction "P1.12_B18") (pintype "bidirectional"))
    )
    (net (code "70") (name "/P1.13") (class "Default")
      (node (ref "U1") (pin "A17") (pinfunction "P1.13_A17") (pintype "bidirectional"))
    )
    (net (code "71") (name "/P1.14") (class "Default")
      (node (ref "U1") (pin "B16") (pinfunction "P1.14_B16") (pintype "bidirectional"))
    )
    (net (code "72") (name "/P1.15") (class "Default")
      (node (ref "U1") (pin "B14") (pinfunction "P1.15_B14") (pintype "bidirectional"))
    )
    (net (code "73") (name "/PMIC_MODE") (class "Default")
      (node (ref "SB7") (pin "1") (pinfunction "0_1") (pintype "passive"))
    )
    (net (code "74") (name "/RF") (class "Default")
      (node (ref "C21") (pin "2") (pinfunction "2_2") (pintype "passive"))
      (node (ref "L1") (pin "1") (pinfunction "1_1") (pintype "passive"))
    )
    (net (code "75") (name "/SWDCLK") (class "Default")
      (node (ref "TP10") (pin "1") (pinfunction "1_1") (pintype "passive"))
      (node (ref "U1") (pin "W31") (pinfunction "SWDCLK_W31") (pintype "input"))
    )
    (net (code "76") (name "/SWDIO") (class "Default")
      (node (ref "TP9") (pin "1") (pinfunction "1_1") (pintype "passive"))
      (node (ref "U1") (pin "AA31") (pinfunction "SWDIO_AA31") (pintype "bidirectional"))
    )
    (net (code "77") (name "/XC1") (class "Default")
      (node (ref "U1") (pin "C31") (pinfunction "XC1_C31") (pintype "input"))
      (node (ref "X1") (pin "1") (pinfunction "IN_1") (pintype "passive"))
    )
    (net (code "78") (name "/XC2") (class "Default")
      (node (ref "U1") (pin "B30") (pinfunction "XC2_B30") (pintype "output"))
      (node (ref "X1") (pin "3") (pinfunction "OUT_3") (pintype "passive"))
    )
    (net (code "98") (name "/~{RESET}") (class "Default")
      (node (ref "TP11") (pin "1") (pinfunction "1_1") (pintype "passive"))
      (node (ref "U1") (pin "AC31") (pinfunction "~{RESET}_AC31") (pintype "input"))
    )
    (net (code "99") (name "GND") (class "Default")
      (node (ref "C1") (pin "1") (pinfunction "1_1") (pintype "passive"))
      (node (ref "C10") (pin "2") (pinfunction "2_2") (pintype "passive"))
      (node (ref "C11") (pin "2") (pinfunction "2_2") (pintype "passive"))
      (node (ref "C12") (pin "2") (pinfunction "2_2") (pintype "passive"))
      (node (ref "C13") (pin "2") (pinfunction "2_2") (pintype "passive"))
      (node (ref "C14") (pin "2") (pinfunction "2_2") (pintype "passive"))
      (node (ref "C15") (pin "2") (pinfunction "2_2") (pintype "passive"))
      (node (ref "C16") (pin "1") (pinfunction "1_1") (pintype "passive"))
      (node (ref "C17") (pin "2") (pinfunction "2_2") (pintype "passive"))
      (node (ref "C18") (pin "2") (pinfunction "2_2") (pintype "passive"))
      (node (ref "C2") (pin "2") (pinfunction "2_2") (pintype "passive"))
      (node (ref "C21") (pin "1") (pinfunction "1_1") (pintype "passive"))
      (node (ref "C3") (pin "1") (pinfunction "1_1") (pintype "passive"))
      (node (ref "C4") (pin "2") (pinfunction "2_2") (pintype "passive"))
      (node (ref "C5") (pin "1") (pinfunction "1_1") (pintype "passive"))
      (node (ref "C6") (pin "2") (pinfunction "2_2") (pintype "passive"))
      (node (ref "C7") (pin "1") (pinfunction "1_1") (pintype "passive"))
      (node (ref "C8") (pin "2") (pinfunction "2_2") (pintype "passive"))
      (node (ref "C9") (pin "2") (pinfunction "2_2") (pintype "passive"))
      (node (ref "R7") (pin "1") (pinfunction "1_1") (pintype "passive"))
      (node (ref "U1") (pin "104") (pinfunction "VSS_PAD_104") (pintype "power_in"))
      (node (ref "U1") (pin "A25") (pinfunction "N.C._A25") (pintype "passive"))
      (node (ref "U1") (pin "B12") (pinfunction "N.C._B12") (pintype "passive"))
      (node (ref "U1") (pin "B26") (pinfunction "N.C._B26") (pintype "passive"))
      (node (ref "U1") (pin "G1") (pinfunction "N.C._G1") (pintype "passive"))
      (node (ref "U1") (pin "H2") (pinfunction "N.C._H2") (pintype "passive"))
      (node (ref "U1") (pin "J31") (pinfunction "N.C._J31") (pintype "passive"))
      (node (ref "X1") (pin "2") (pinfunction "GND_2") (pintype "passive"))
      (node (ref "X1") (pin "4") (pinfunction "GND_4") (pintype "passive"))
    )
    (net (code "100") (name "Net-(SB7-1)") (class "Default")
      (node (ref "R7") (pin "2") (pinfunction "2_2") (pintype "passive"))
      (node (ref "SB7") (pin "2") (pinfunction "1_2") (pintype "passive"))
      (node (ref "TP30") (pin "1") (pinfunction "1_1") (pintype "passive"))
    )
    (net (code "101") (name "Net-(U1A-DCC)") (class "Default")
      (node (ref "L2") (pin "2") (pinfunction "2_2") (pintype "passive"))
      (node (ref "U1") (pin "A21") (pinfunction "DCC_A21") (pintype "output"))
    )
    (net (code "102") (name "Net-(U1A-DCCD)") (class "Default")
      (node (ref "L3") (pin "2") (pinfunction "2_2") (pintype "passive"))
      (node (ref "U1") (pin "B10") (pinfunction "DCCD_B10") (pintype "power_in"))
    )
    (net (code "103") (name "Net-(U1A-DECA)") (class "Default")
      (node (ref "C7") (pin "2") (pinfunction "2_2") (pintype "passive"))
      (node (ref "U1") (pin "A13") (pinfunction "DECA_A13") (pintype "power_in"))
    )
    (net (code "104") (name "Net-(U1A-DECD)") (class "Default")
      (node (ref "C5") (pin "2") (pinfunction "2_2") (pintype "passive"))
      (node (ref "L3") (pin "1") (pinfunction "1_1") (pintype "passive"))
      (node (ref "U1") (pin "A15") (pinfunction "DECD_A15") (pintype "power_in"))
    )
    (net (code "105") (name "Net-(U1A-DECN)") (class "Default")
      (node (ref "C6") (pin "1") (pinfunction "1_1") (pintype "passive"))
      (node (ref "U1") (pin "A23") (pinfunction "DECN_A23") (pintype "power_in"))
    )
    (net (code "106") (name "Net-(U1A-DECR)") (class "Default")
      (node (ref "C3") (pin "2") (pinfunction "2_2") (pintype "passive"))
      (node (ref "C4") (pin "1") (pinfunction "1_1") (pintype "passive"))
      (node (ref "L2") (pin "1") (pinfunction "1_1") (pintype "passive"))
      (node (ref "U1") (pin "A27") (pinfunction "DECR_A27") (pintype "power_in"))
      (node (ref "U1") (pin "G31") (pinfunction "DECRF_G31") (pintype "power_in"))
    )
    (net (code "107") (name "Net-(U1A-DECUSB)") (class "Default")
      (node (ref "C18") (pin "1") (pinfunction "1_1") (pintype "passive"))
      (node (ref "U1") (pin "B6") (pinfunction "DECUSB_B6") (pintype "power_in"))
    )
    (net (code "108") (name "Net-(U1A-VBUS)") (class "Default")
      (node (ref "C17") (pin "1") (pinfunction "1_1") (pintype "passive"))
      (node (ref "R1") (pin "2") (pinfunction "2_2") (pintype "passive"))
      (node (ref "U1") (pin "A5") (pinfunction "VBUS_A5") (pintype "power_in"))
    )
    (net (code "109") (name "VBUS") (class "Default")
      (node (ref "R1") (pin "1") (pinfunction "1_1") (pintype "passive"))
    )
    (net (code "110") (name "VDD_nRF53") (class "Default")
      (node (ref "C10") (pin "1") (pinfunction "1_1") (pintype "passive"))
      (node (ref "C11") (pin "1") (pinfunction "1_1") (pintype "passive"))
      (node (ref "C12") (pin "1") (pinfunction "1_1") (pintype "passive"))
      (node (ref "C13") (pin "1") (pinfunction "1_1") (pintype "passive"))
      (node (ref "C14") (pin "1") (pinfunction "1_1") (pintype "passive"))
      (node (ref "C15") (pin "1") (pinfunction "1_1") (pintype "passive"))
      (node (ref "C16") (pin "2") (pinfunction "2_2") (pintype "passive"))
      (node (ref "C2") (pin "1") (pinfunction "1_1") (pintype "passive"))
      (node (ref "C8") (pin "1") (pinfunction "1_1") (pintype "passive"))
      (node (ref "C9") (pin "1") (pinfunction "1_1") (pintype "passive"))
      (node (ref "U1") (pin "A19") (pinfunction "VDD_A19") (pintype "power_in"))
      (node (ref "U1") (pin "AC1") (pinfunction "VDD_AC1") (pintype "power_in"))
      (node (ref "U1") (pin "AG1") (pinfunction "VDD_AG1") (pintype "power_in"))
      (node (ref "U1") (pin "AJ31") (pinfunction "VDD_AJ31") (pintype "power_in"))
      (node (ref "U1") (pin "AL11") (pinfunction "VDD_AL11") (pintype "power_in"))
      (node (ref "U1") (pin "AL17") (pinfunction "VDD_AL17") (pintype "power_in"))
      (node (ref "U1") (pin "AL25") (pinfunction "VDD_AL25") (pintype "power_in"))
      (node (ref "U1") (pin "AL3") (pinfunction "VDD_AL3") (pintype "power_in"))
      (node (ref "U1") (pin "AL7") (pinfunction "VDD_AL7") (pintype "power_in"))
      (node (ref "U1") (pin "B28") (pinfunction "VDD_B28") (pintype "power_in"))
      (node (ref "U1") (pin "B8") (pinfunction "VDD_B8") (pintype "power_in"))
      (node (ref "U1") (pin "C1") (pinfunction "VDD_C1") (pintype "power_in"))
      (node (ref "U1") (pin "E1") (pinfunction "VDDH_E1") (pintype "power_in"))
      (node (ref "U1") (pin "E31") (pinfunction "VDD_E31") (pintype "power_in"))
      (node (ref "U1") (pin "L1") (pinfunction "VDD_L1") (pintype "power_in"))
      (node (ref "U1") (pin "N31") (pinfunction "VDD_N31") (pintype "power_in"))
      (node (ref "U1") (pin "U1") (pinfunction "VDD_U1") (pintype "power_in"))
    )
    (net (code "111") (name "unconnected-(U1A-DCCH-PadJ1)") (class "Default")
      (node (ref "U1") (pin "J1") (pinfunction "DCCH_J1") (pintype "power_in"))
    )
    (net (code "112") (name "unconnected-(U1D-N.C.-PadA1)") (class "Default")
      (node (ref "U1") (pin "A1") (pinfunction "N.C._A1") (pintype "passive"))
    )
    (net (code "113") (name "unconnected-(U1D-N.C.-PadA31)") (class "Default")
      (node (ref "U1") (pin "A31") (pinfunction "N.C._A31") (pintype "passive"))
    )
    (net (code "114") (name "unconnected-(U1D-N.C.-PadAG31)") (class "Default")
      (node (ref "U1") (pin "AG31") (pinfunction "N.C._AG31") (pintype "passive"))
    )
    (net (code "115") (name "unconnected-(U1D-N.C.-PadAL1)") (class "Default")
      (node (ref "U1") (pin "AL1") (pinfunction "N.C._AL1") (pintype "passive"))
    )
    (net (code "116") (name "unconnected-(U1D-N.C.-PadAL31)") (class "Default")
      (node (ref "U1") (pin "AL31") (pinfunction "N.C._AL31") (pintype "passive"))
    )
    (net (code "117") (name "unconnected-(U1D-N.C.-PadD2)") (class "Default")
      (node (ref "U1") (pin "D2") (pinfunction "N.C._D2") (pintype "passive"))
    )
    (net (code "118") (name "unconnected-(U1D-N.C.-PadF2)") (class "Default")
      (node (ref "U1") (pin "F2") (pinfunction "N.C._F2") (pintype "passive"))
    )
    (net (code "119") (name "unconnected-(U1D-N.C.-PadT2)") (class "Default")
      (node (ref "U1") (pin "T2") (pinfunction "N.C._T2") (pintype "passive"))
    )
  )
)
